# ngptv-lite-v11.net
KiCad netlist of a schematic drawn in EAGLE
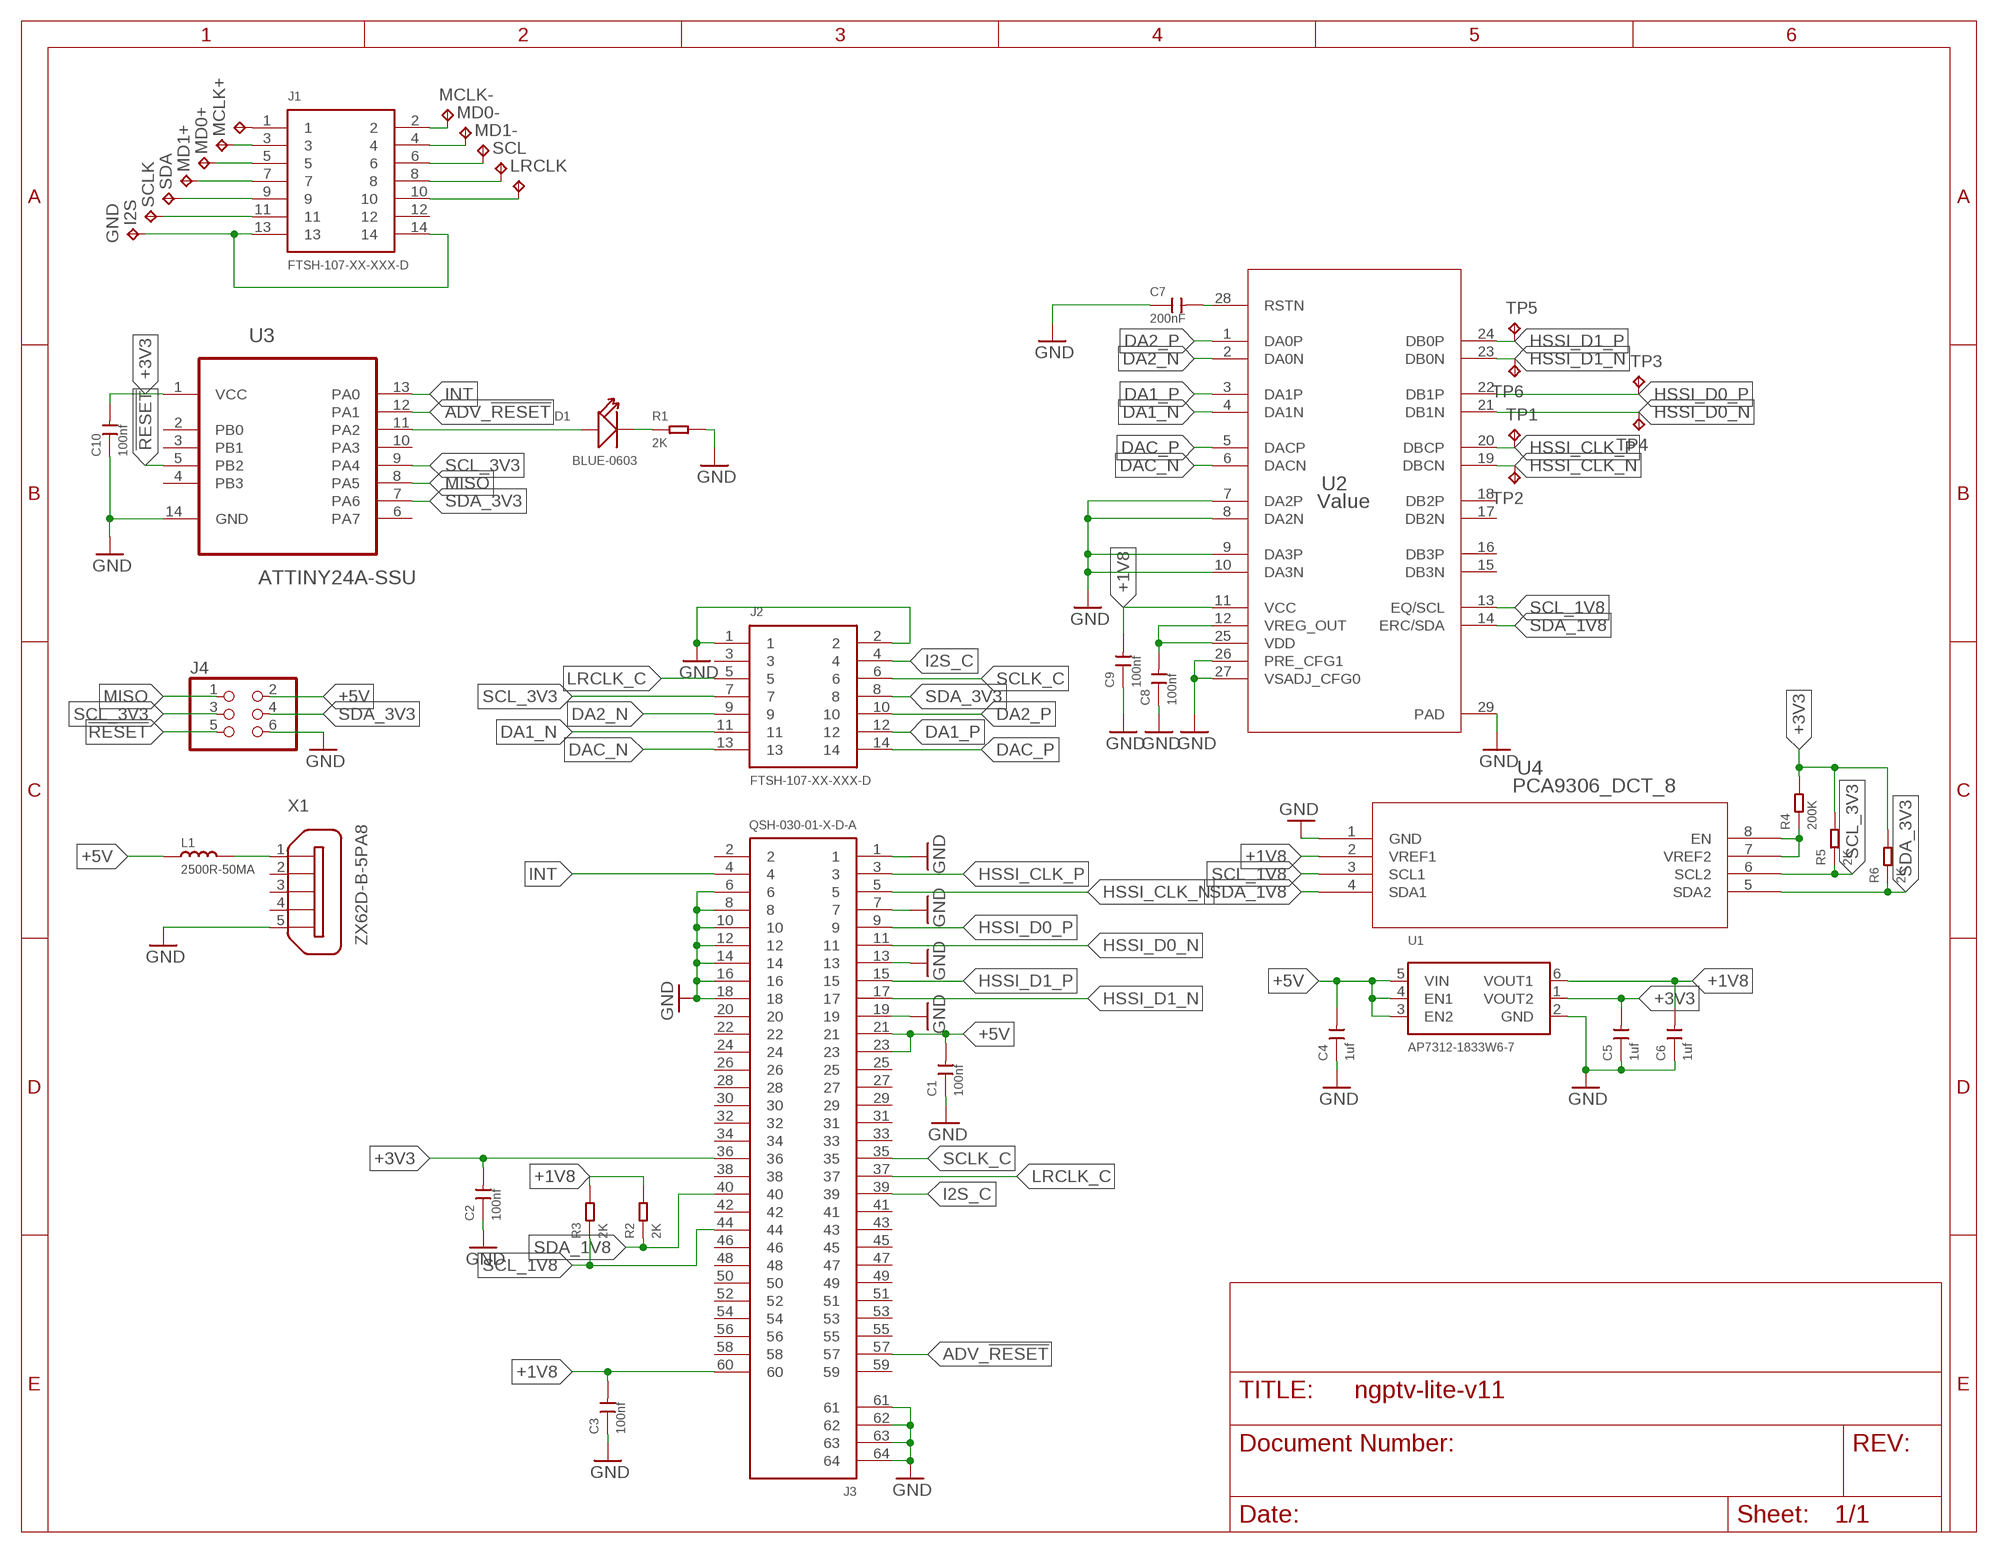
[diagram p0: schematic, sheet 1]

(export (version "E")
  (design (tool "Eeschema 10.0.6"))
  (components
    (comp (ref "C1")
      (value "100nf")
      (footprint "eagle-import:C0603")
      (fields (field (name "MPN") "CC0603KRX7R9BB104"))
      (libsource (lib "eagle-import") (part "CERAMIC-100NF-50V-10%-X7R(0603)"))
    )
    (comp (ref "C2")
      (value "100nf")
      (footprint "eagle-import:C0603")
      (fields (field (name "MPN") "CC0603KRX7R9BB104"))
      (libsource (lib "eagle-import") (part "CERAMIC-100NF-50V-10%-X7R(0603)"))
    )
    (comp (ref "C3")
      (value "100nf")
      (footprint "eagle-import:C0603")
      (fields (field (name "MPN") "CC0603KRX7R9BB104"))
      (libsource (lib "eagle-import") (part "CERAMIC-100NF-50V-10%-X7R(0603)"))
    )
    (comp (ref "C4")
      (value "1uf")
      (footprint "eagle-import:C0603")
      (fields (field (name "MPN") "CC0603KRX7R8BB105"))
      (libsource (lib "eagle-import") (part "CERAMIC-1UF-25V-10%-X7R(0603)"))
    )
    (comp (ref "C5")
      (value "1uf")
      (footprint "eagle-import:C0603")
      (fields (field (name "MPN") "CC0603KRX7R8BB105"))
      (libsource (lib "eagle-import") (part "CERAMIC-1UF-25V-10%-X7R(0603)"))
    )
    (comp (ref "C6")
      (value "1uf")
      (footprint "eagle-import:C0603")
      (fields (field (name "MPN") "CC0603KRX7R8BB105"))
      (libsource (lib "eagle-import") (part "CERAMIC-1UF-25V-10%-X7R(0603)"))
    )
    (comp (ref "C7")
      (value "200nF")
      (footprint "eagle-import:C0603")
      (fields (field (name "MPN") "CC0603KRX7R8BB224"))
      (libsource (lib "eagle-import") (part "CERAMIC-220NF-25V-10%-X7R(0603)"))
    )
    (comp (ref "C8")
      (value "100nf")
      (footprint "eagle-import:C0603")
      (fields (field (name "MPN") "CC0603KRX7R9BB104"))
      (libsource (lib "eagle-import") (part "CERAMIC-100NF-50V-10%-X7R(0603)"))
    )
    (comp (ref "C9")
      (value "100nf")
      (footprint "eagle-import:C0603")
      (fields (field (name "MPN") "CC0603KRX7R9BB104"))
      (libsource (lib "eagle-import") (part "CERAMIC-100NF-50V-10%-X7R(0603)"))
    )
    (comp (ref "C10")
      (value "100nf")
      (footprint "eagle-import:C0603")
      (fields (field (name "MPN") "CC0603KRX7R9BB104"))
      (libsource (lib "eagle-import") (part "CERAMIC-100NF-50V-10%-X7R(0603)"))
    )
    (comp (ref "D1")
      (value "BLUE-0603")
      (footprint "eagle-import:LED-0603")
      (fields (field (name "MPN") "19-217-BHC-ZL1M2RY-3T"))
      (libsource (lib "eagle-import") (part "SMD-LED-CLEAR-BLUE(0603)"))
    )
    (comp (ref "GND")
      (value "TPTP14R")
      (footprint "eagle-import:TP14R")
      (libsource (lib "eagle-import") (part "TPTP14R"))
    )
    (comp (ref "I2S")
      (value "TPTP12R")
      (footprint "eagle-import:TP12R")
      (libsource (lib "eagle-import") (part "TPTP12R"))
    )
    (comp (ref "J1")
      (value "FTSH-107-XX-XXX-D")
      (footprint "eagle-import:FTSH-107-XX-XXX-D")
      (libsource (lib "eagle-import") (part "FTSH-107-XX-XXX-D"))
    )
    (comp (ref "J2")
      (value "FTSH-107-XX-XXX-D")
      (footprint "eagle-import:FTSH-107-XX-XXX-D")
      (libsource (lib "eagle-import") (part "FTSH-107-XX-XXX-D"))
    )
    (comp (ref "J3")
      (value "QSH-030-01-X-D-A")
      (footprint "eagle-import:QSH-030-01-X-D-A")
      (libsource (lib "eagle-import") (part "QSH-030-01-X-D-A"))
    )
    (comp (ref "J4")
      (value "PINHD-2X3/90")
      (footprint "eagle-import:2X03_90")
      (libsource (lib "eagle-import") (part "PINHD-2X3/90"))
    )
    (comp (ref "L1")
      (value "2500R-50MA")
      (footprint "eagle-import:L0603")
      (libsource (lib "eagle-import") (part "SMD-FERRITE-BEAD-2500R-50MA(0603)"))
    )
    (comp (ref "LRCLK")
      (value "TPTP12R")
      (footprint "eagle-import:TP12R")
      (libsource (lib "eagle-import") (part "TPTP12R"))
    )
    (comp (ref "MCLK+")
      (value "TPTP12R")
      (footprint "eagle-import:TP12R")
      (libsource (lib "eagle-import") (part "TPTP12R"))
    )
    (comp (ref "MCLK-")
      (value "TPTP12R")
      (footprint "eagle-import:TP12R")
      (libsource (lib "eagle-import") (part "TPTP12R"))
    )
    (comp (ref "MD0+")
      (value "TPTP12R")
      (footprint "eagle-import:TP12R")
      (libsource (lib "eagle-import") (part "TPTP12R"))
    )
    (comp (ref "MD0-")
      (value "TPTP12R")
      (footprint "eagle-import:TP12R")
      (libsource (lib "eagle-import") (part "TPTP12R"))
    )
    (comp (ref "MD1+")
      (value "TPTP12R")
      (footprint "eagle-import:TP12R")
      (libsource (lib "eagle-import") (part "TPTP12R"))
    )
    (comp (ref "MD1-")
      (value "TPTP12R")
      (footprint "eagle-import:TP12R")
      (libsource (lib "eagle-import") (part "TPTP12R"))
    )
    (comp (ref "R1")
      (value "2K")
      (footprint "eagle-import:R0603")
      (fields (field (name "MPN") "RC0603FR-071KL"))
      (libsource (lib "eagle-import") (part "SMD-RES-1K-1%-1/10W(0603)"))
    )
    (comp (ref "R2")
      (value "2K")
      (footprint "eagle-import:R0603")
      (fields (field (name "MPN") "RC0603JR-072KL"))
      (libsource (lib "eagle-import") (part "SMD-RES-2K-5%-1/10W(0603)"))
    )
    (comp (ref "R3")
      (value "2K")
      (footprint "eagle-import:R0603")
      (fields (field (name "MPN") "RC0603JR-072KL"))
      (libsource (lib "eagle-import") (part "SMD-RES-2K-5%-1/10W(0603)"))
    )
    (comp (ref "R4")
      (value "200K")
      (footprint "eagle-import:R0603")
      (fields (field (name "MPN") "RC0603JR-07200KL"))
      (libsource (lib "eagle-import") (part "SMD-RES-200K-5%-1/10W(0603)"))
    )
    (comp (ref "R5")
      (value "2K")
      (footprint "eagle-import:R0603")
      (fields (field (name "MPN") "RC0603JR-072KL"))
      (libsource (lib "eagle-import") (part "SMD-RES-2K-5%-1/10W(0603)"))
    )
    (comp (ref "R6")
      (value "2K")
      (footprint "eagle-import:R0603")
      (fields (field (name "MPN") "RC0603JR-072KL"))
      (libsource (lib "eagle-import") (part "SMD-RES-2K-5%-1/10W(0603)"))
    )
    (comp (ref "SCL")
      (value "TPTP12R")
      (footprint "eagle-import:TP12R")
      (libsource (lib "eagle-import") (part "TPTP12R"))
    )
    (comp (ref "SCLK")
      (value "TPTP12R")
      (footprint "eagle-import:TP12R")
      (libsource (lib "eagle-import") (part "TPTP12R"))
    )
    (comp (ref "SDA")
      (value "TPTP12R")
      (footprint "eagle-import:TP12R")
      (libsource (lib "eagle-import") (part "TPTP12R"))
    )
    (comp (ref "TP1")
      (value "TPTP06SQ")
      (footprint "eagle-import:TP06SQ")
      (libsource (lib "eagle-import") (part "TPTP06SQ"))
    )
    (comp (ref "TP2")
      (value "TPTP06SQ")
      (footprint "eagle-import:TP06SQ")
      (libsource (lib "eagle-import") (part "TPTP06SQ"))
    )
    (comp (ref "TP3")
      (value "TPTP06SQ")
      (footprint "eagle-import:TP06SQ")
      (libsource (lib "eagle-import") (part "TPTP06SQ"))
    )
    (comp (ref "TP4")
      (value "TPTP06SQ")
      (footprint "eagle-import:TP06SQ")
      (libsource (lib "eagle-import") (part "TPTP06SQ"))
    )
    (comp (ref "TP5")
      (value "TPTP06SQ")
      (footprint "eagle-import:TP06SQ")
      (libsource (lib "eagle-import") (part "TPTP06SQ"))
    )
    (comp (ref "TP6")
      (value "TPTP06SQ")
      (footprint "eagle-import:TP06SQ")
      (libsource (lib "eagle-import") (part "TPTP06SQ"))
    )
    (comp (ref "U1")
      (value "AP7312-1833W6-7")
      (footprint "eagle-import:SOT95P280X145-6N")
      (libsource (lib "eagle-import") (part "AP7312"))
    )
    (comp (ref "U2")
      (value "Value")
      (footprint "eagle-import:RHR0028A_NV")
      (fields
        (field (name "ALTERNATEPARTNUMBER") "SN65DPHY440SS")
        (field (name "MANUFACTURER") "Texas Instruments")
        (field (name "PARTNUMBER") "SN75DPHY440SS")
      )
      (libsource (lib "eagle-import") (part "SN75DPHY440SS"))
    )
    (comp (ref "U3")
      (value "ATTINY24A-SSU")
      (footprint "eagle-import:SOIC127P600X175-14N")
      (libsource (lib "eagle-import") (part "ATTINY24A-SSU"))
    )
    (comp (ref "U4")
      (value "PCA9306_DCT_8")
      (footprint "eagle-import:DCT8")
      (fields
        (field (name "GENERIC_PART_NUMBER") "PCA9306")
        (field (name "MANUFACTURER") "Texas Instruments")
        (field (name "MANUFACTURER_PART_NUMBER") "pca9306_dct_8")
      )
      (libsource (lib "eagle-import") (part "PCA9306_DCT_8"))
    )
    (comp (ref "X1")
      (value "ZX62D-B-5PA8")
      (footprint "eagle-import:ZX62D-B-5PA8")
      (fields (field (name "MF") "Hirose"))
      (libsource (lib "eagle-import") (part "ZX62D-B-5PA8"))
    )
  )
  (nets
    (net (code "1") (name "+1V8") (class "Default")
      (node (ref "C3") (pin "2") (pinfunction "2_2") (pintype "passive"))
      (node (ref "C6") (pin "2") (pinfunction "2_2") (pintype "passive"))
      (node (ref "C9") (pin "2") (pinfunction "2_2") (pintype "passive"))
      (node (ref "J3") (pin "60") (pinfunction "60_60") (pintype "bidirectional"))
      (node (ref "R2") (pin "2") (pinfunction "2_2") (pintype "passive"))
      (node (ref "R3") (pin "2") (pinfunction "2_2") (pintype "passive"))
      (node (ref "U1") (pin "6") (pinfunction "VOUT1_6") (pintype "power_in"))
      (node (ref "U2") (pin "11") (pinfunction "VCC_11") (pintype "power_in"))
      (node (ref "U4") (pin "2") (pinfunction "VREF1_2") (pintype "power_in"))
    )
    (net (code "2") (name "+3V3") (class "Default")
      (node (ref "C10") (pin "2") (pinfunction "2_2") (pintype "passive"))
      (node (ref "C2") (pin "2") (pinfunction "2_2") (pintype "passive"))
      (node (ref "C5") (pin "2") (pinfunction "2_2") (pintype "passive"))
      (node (ref "J3") (pin "36") (pinfunction "36_36") (pintype "bidirectional"))
      (node (ref "R4") (pin "2") (pinfunction "2_2") (pintype "passive"))
      (node (ref "R5") (pin "2") (pinfunction "2_2") (pintype "passive"))
      (node (ref "R6") (pin "2") (pinfunction "2_2") (pintype "passive"))
      (node (ref "U1") (pin "1") (pinfunction "VOUT2_1") (pintype "power_in"))
      (node (ref "U3") (pin "1") (pinfunction "VCC_1") (pintype "power_in"))
    )
    (net (code "3") (name "+5V") (class "Default")
      (node (ref "C1") (pin "2") (pinfunction "2_2") (pintype "passive"))
      (node (ref "C4") (pin "2") (pinfunction "2_2") (pintype "passive"))
      (node (ref "J3") (pin "21") (pinfunction "21_21") (pintype "bidirectional"))
      (node (ref "J3") (pin "23") (pinfunction "23_23") (pintype "bidirectional"))
      (node (ref "J4") (pin "2") (pinfunction "2_2") (pintype "passive"))
      (node (ref "L1") (pin "1") (pinfunction "1_1") (pintype "passive"))
      (node (ref "U1") (pin "3") (pinfunction "EN2_3") (pintype "bidirectional"))
      (node (ref "U1") (pin "4") (pinfunction "EN1_4") (pintype "bidirectional"))
      (node (ref "U1") (pin "5") (pinfunction "VIN_5") (pintype "power_in"))
    )
    (net (code "4") (name "/ADV_~{RESET}") (class "Default")
      (node (ref "J3") (pin "57") (pinfunction "57_57") (pintype "bidirectional"))
      (node (ref "U3") (pin "12") (pinfunction "PA1_12") (pintype "bidirectional"))
    )
    (net (code "5") (name "/~{RESET}") (class "Default")
      (node (ref "J4") (pin "5") (pinfunction "5_5") (pintype "passive"))
      (node (ref "U3") (pin "5") (pinfunction "PB2_5") (pintype "bidirectional"))
    )
    (net (code "6") (name "DA1_N") (class "Default")
      (node (ref "J2") (pin "11") (pinfunction "11_11") (pintype "bidirectional"))
      (node (ref "U2") (pin "4") (pinfunction "DA1N_4") (pintype "bidirectional"))
    )
    (net (code "7") (name "DA1_P") (class "Default")
      (node (ref "J2") (pin "12") (pinfunction "12_12") (pintype "bidirectional"))
      (node (ref "U2") (pin "3") (pinfunction "DA1P_3") (pintype "bidirectional"))
    )
    (net (code "8") (name "DA2_N") (class "Default")
      (node (ref "J2") (pin "9") (pinfunction "9_9") (pintype "bidirectional"))
      (node (ref "U2") (pin "2") (pinfunction "DA0N_2") (pintype "bidirectional"))
    )
    (net (code "9") (name "DA2_P") (class "Default")
      (node (ref "J2") (pin "10") (pinfunction "10_10") (pintype "bidirectional"))
      (node (ref "U2") (pin "1") (pinfunction "DA0P_1") (pintype "bidirectional"))
    )
    (net (code "10") (name "DAC_N") (class "Default")
      (node (ref "J2") (pin "13") (pinfunction "13_13") (pintype "bidirectional"))
      (node (ref "U2") (pin "6") (pinfunction "DACN_6") (pintype "bidirectional"))
    )
    (net (code "11") (name "DAC_P") (class "Default")
      (node (ref "J2") (pin "14") (pinfunction "14_14") (pintype "bidirectional"))
      (node (ref "U2") (pin "5") (pinfunction "DACP_5") (pintype "bidirectional"))
    )
    (net (code "12") (name "GND") (class "Default")
      (node (ref "C1") (pin "1") (pinfunction "1_1") (pintype "passive"))
      (node (ref "C10") (pin "1") (pinfunction "1_1") (pintype "passive"))
      (node (ref "C2") (pin "1") (pinfunction "1_1") (pintype "passive"))
      (node (ref "C3") (pin "1") (pinfunction "1_1") (pintype "passive"))
      (node (ref "C4") (pin "1") (pinfunction "1_1") (pintype "passive"))
      (node (ref "C5") (pin "1") (pinfunction "1_1") (pintype "passive"))
      (node (ref "C6") (pin "1") (pinfunction "1_1") (pintype "passive"))
      (node (ref "C7") (pin "1") (pinfunction "1_1") (pintype "passive"))
      (node (ref "C8") (pin "1") (pinfunction "1_1") (pintype "passive"))
      (node (ref "C9") (pin "1") (pinfunction "1_1") (pintype "passive"))
      (node (ref "J2") (pin "1") (pinfunction "1_1") (pintype "bidirectional"))
      (node (ref "J2") (pin "2") (pinfunction "2_2") (pintype "bidirectional"))
      (node (ref "J3") (pin "1") (pinfunction "1_1") (pintype "bidirectional"))
      (node (ref "J3") (pin "10") (pinfunction "10_10") (pintype "bidirectional"))
      (node (ref "J3") (pin "12") (pinfunction "12_12") (pintype "bidirectional"))
      (node (ref "J3") (pin "13") (pinfunction "13_13") (pintype "bidirectional"))
      (node (ref "J3") (pin "14") (pinfunction "14_14") (pintype "bidirectional"))
      (node (ref "J3") (pin "16") (pinfunction "16_16") (pintype "bidirectional"))
      (node (ref "J3") (pin "18") (pinfunction "18_18") (pintype "bidirectional"))
      (node (ref "J3") (pin "19") (pinfunction "19_19") (pintype "bidirectional"))
      (node (ref "J3") (pin "6") (pinfunction "6_6") (pintype "bidirectional"))
      (node (ref "J3") (pin "61") (pinfunction "61_61") (pintype "power_in"))
      (node (ref "J3") (pin "62") (pinfunction "62_62") (pintype "power_in"))
      (node (ref "J3") (pin "63") (pinfunction "63_63") (pintype "power_in"))
      (node (ref "J3") (pin "64") (pinfunction "64_64") (pintype "power_in"))
      (node (ref "J3") (pin "7") (pinfunction "7_7") (pintype "bidirectional"))
      (node (ref "J3") (pin "8") (pinfunction "8_8") (pintype "bidirectional"))
      (node (ref "J4") (pin "6") (pinfunction "6_6") (pintype "passive"))
      (node (ref "R1") (pin "2") (pinfunction "2_2") (pintype "passive"))
      (node (ref "U1") (pin "2") (pinfunction "GND_2") (pintype "bidirectional"))
      (node (ref "U2") (pin "10") (pinfunction "DA3N_10") (pintype "bidirectional"))
      (node (ref "U2") (pin "26") (pinfunction "PRE_CFG1_26") (pintype "bidirectional"))
      (node (ref "U2") (pin "27") (pinfunction "VSADJ_CFG0_27") (pintype "bidirectional"))
      (node (ref "U2") (pin "29") (pinfunction "PAD_29") (pintype "power_in"))
      (node (ref "U2") (pin "7") (pinfunction "DA2P_7") (pintype "bidirectional"))
      (node (ref "U2") (pin "8") (pinfunction "DA2N_8") (pintype "bidirectional"))
      (node (ref "U2") (pin "9") (pinfunction "DA3P_9") (pintype "bidirectional"))
      (node (ref "U3") (pin "14") (pinfunction "GND_14") (pintype "power_in"))
      (node (ref "U4") (pin "1") (pinfunction "GND_1") (pintype "power_in"))
      (node (ref "X1") (pin "5") (pinfunction "5_5") (pintype "passive"))
    )
    (net (code "13") (name "HSSI_CLK_N") (class "Default")
      (node (ref "J3") (pin "5") (pinfunction "5_5") (pintype "bidirectional"))
      (node (ref "TP2") (pin "TP") (pinfunction "TP_TP") (pintype "input"))
      (node (ref "U2") (pin "19") (pinfunction "DBCN_19") (pintype "bidirectional"))
    )
    (net (code "14") (name "HSSI_CLK_P") (class "Default")
      (node (ref "J3") (pin "3") (pinfunction "3_3") (pintype "bidirectional"))
      (node (ref "TP1") (pin "TP") (pinfunction "TP_TP") (pintype "input"))
      (node (ref "U2") (pin "20") (pinfunction "DBCP_20") (pintype "bidirectional"))
    )
    (net (code "15") (name "HSSI_D0_N") (class "Default")
      (node (ref "J3") (pin "11") (pinfunction "11_11") (pintype "bidirectional"))
      (node (ref "TP4") (pin "TP") (pinfunction "TP_TP") (pintype "input"))
      (node (ref "U2") (pin "21") (pinfunction "DB1N_21") (pintype "bidirectional"))
    )
    (net (code "16") (name "HSSI_D0_P") (class "Default")
      (node (ref "J3") (pin "9") (pinfunction "9_9") (pintype "bidirectional"))
      (node (ref "TP3") (pin "TP") (pinfunction "TP_TP") (pintype "input"))
      (node (ref "U2") (pin "22") (pinfunction "DB1P_22") (pintype "bidirectional"))
    )
    (net (code "17") (name "HSSI_D1_N") (class "Default")
      (node (ref "J3") (pin "17") (pinfunction "17_17") (pintype "bidirectional"))
      (node (ref "TP6") (pin "TP") (pinfunction "TP_TP") (pintype "input"))
      (node (ref "U2") (pin "23") (pinfunction "DB0N_23") (pintype "bidirectional"))
    )
    (net (code "18") (name "HSSI_D1_P") (class "Default")
      (node (ref "J3") (pin "15") (pinfunction "15_15") (pintype "bidirectional"))
      (node (ref "TP5") (pin "TP") (pinfunction "TP_TP") (pintype "input"))
      (node (ref "U2") (pin "24") (pinfunction "DB0P_24") (pintype "bidirectional"))
    )
    (net (code "19") (name "I2S_C") (class "Default")
      (node (ref "J2") (pin "4") (pinfunction "4_4") (pintype "bidirectional"))
      (node (ref "J3") (pin "39") (pinfunction "39_39") (pintype "bidirectional"))
    )
    (net (code "20") (name "INT") (class "Default")
      (node (ref "J3") (pin "4") (pinfunction "4_4") (pintype "bidirectional"))
      (node (ref "U3") (pin "13") (pinfunction "PA0_13") (pintype "bidirectional"))
    )
    (net (code "21") (name "LRCLK_C") (class "Default")
      (node (ref "J2") (pin "5") (pinfunction "5_5") (pintype "bidirectional"))
      (node (ref "J3") (pin "37") (pinfunction "37_37") (pintype "bidirectional"))
    )
    (net (code "22") (name "MISO") (class "Default")
      (node (ref "J4") (pin "1") (pinfunction "1_1") (pintype "passive"))
      (node (ref "U3") (pin "8") (pinfunction "PA5_8") (pintype "bidirectional"))
    )
    (net (code "23") (name "Net-(D1-Pad-)") (class "Default")
      (node (ref "D1") (pin "-") (pinfunction "-_-") (pintype "passive"))
      (node (ref "R1") (pin "1") (pinfunction "1_1") (pintype "passive"))
    )
    (net (code "24") (name "Net-(GND-PadTP)") (class "Default")
      (node (ref "GND") (pin "TP") (pinfunction "TP_TP") (pintype "input"))
      (node (ref "J1") (pin "13") (pinfunction "13_13") (pintype "bidirectional"))
      (node (ref "J1") (pin "14") (pinfunction "14_14") (pintype "bidirectional"))
    )
    (net (code "25") (name "Net-(I2S-PadTP)") (class "Default")
      (node (ref "I2S") (pin "TP") (pinfunction "TP_TP") (pintype "input"))
      (node (ref "J1") (pin "11") (pinfunction "11_11") (pintype "bidirectional"))
    )
    (net (code "26") (name "Net-(J1-Pad1)") (class "Default")
      (node (ref "J1") (pin "1") (pinfunction "1_1") (pintype "bidirectional"))
      (node (ref "MCLK+") (pin "TP") (pinfunction "TP_TP") (pintype "input"))
    )
    (net (code "27") (name "Net-(J1-Pad2)") (class "Default")
      (node (ref "J1") (pin "2") (pinfunction "2_2") (pintype "bidirectional"))
      (node (ref "MCLK-") (pin "TP") (pinfunction "TP_TP") (pintype "input"))
    )
    (net (code "28") (name "Net-(J1-Pad3)") (class "Default")
      (node (ref "J1") (pin "3") (pinfunction "3_3") (pintype "bidirectional"))
      (node (ref "MD0+") (pin "TP") (pinfunction "TP_TP") (pintype "input"))
    )
    (net (code "29") (name "Net-(J1-Pad4)") (class "Default")
      (node (ref "J1") (pin "4") (pinfunction "4_4") (pintype "bidirectional"))
      (node (ref "MD0-") (pin "TP") (pinfunction "TP_TP") (pintype "input"))
    )
    (net (code "30") (name "Net-(J1-Pad5)") (class "Default")
      (node (ref "J1") (pin "5") (pinfunction "5_5") (pintype "bidirectional"))
      (node (ref "MD1+") (pin "TP") (pinfunction "TP_TP") (pintype "input"))
    )
    (net (code "31") (name "Net-(J1-Pad6)") (class "Default")
      (node (ref "J1") (pin "6") (pinfunction "6_6") (pintype "bidirectional"))
      (node (ref "MD1-") (pin "TP") (pinfunction "TP_TP") (pintype "input"))
    )
    (net (code "32") (name "Net-(J1-Pad7)") (class "Default")
      (node (ref "J1") (pin "7") (pinfunction "7_7") (pintype "bidirectional"))
      (node (ref "SDA") (pin "TP") (pinfunction "TP_TP") (pintype "input"))
    )
    (net (code "33") (name "Net-(J1-Pad8)") (class "Default")
      (node (ref "J1") (pin "8") (pinfunction "8_8") (pintype "bidirectional"))
      (node (ref "SCL") (pin "TP") (pinfunction "TP_TP") (pintype "input"))
    )
    (net (code "34") (name "Net-(J1-Pad9)") (class "Default")
      (node (ref "J1") (pin "9") (pinfunction "9_9") (pintype "bidirectional"))
      (node (ref "SCLK") (pin "TP") (pinfunction "TP_TP") (pintype "input"))
    )
    (net (code "35") (name "Net-(J1-Pad10)") (class "Default")
      (node (ref "J1") (pin "10") (pinfunction "10_10") (pintype "bidirectional"))
      (node (ref "LRCLK") (pin "TP") (pinfunction "TP_TP") (pintype "input"))
    )
    (net (code "36") (name "Net-(L1-Pad2)") (class "Default")
      (node (ref "L1") (pin "2") (pinfunction "2_2") (pintype "passive"))
      (node (ref "X1") (pin "1") (pinfunction "1_1") (pintype "passive"))
    )
    (net (code "37") (name "Net-(U2-RSTN)") (class "Default")
      (node (ref "C7") (pin "2") (pinfunction "2_2") (pintype "passive"))
      (node (ref "U2") (pin "28") (pinfunction "RSTN_28") (pintype "bidirectional"))
    )
    (net (code "38") (name "Net-(U2-VDD)") (class "Default")
      (node (ref "C8") (pin "2") (pinfunction "2_2") (pintype "passive"))
      (node (ref "U2") (pin "12") (pinfunction "VREG_OUT_12") (pintype "power_in"))
      (node (ref "U2") (pin "25") (pinfunction "VDD_25") (pintype "power_in"))
    )
    (net (code "39") (name "Net-(U3-PA2)") (class "Default")
      (node (ref "D1") (pin "+") (pinfunction "+_+") (pintype "passive"))
      (node (ref "U3") (pin "11") (pinfunction "PA2_11") (pintype "bidirectional"))
    )
    (net (code "40") (name "Net-(U4-EN)") (class "Default")
      (node (ref "R4") (pin "1") (pinfunction "1_1") (pintype "passive"))
      (node (ref "U4") (pin "7") (pinfunction "VREF2_7") (pintype "power_in"))
      (node (ref "U4") (pin "8") (pinfunction "EN_8") (pintype "passive"))
    )
    (net (code "41") (name "SCLK_C") (class "Default")
      (node (ref "J2") (pin "6") (pinfunction "6_6") (pintype "bidirectional"))
      (node (ref "J3") (pin "35") (pinfunction "35_35") (pintype "bidirectional"))
    )
    (net (code "42") (name "SCL_1V8") (class "Default")
      (node (ref "J3") (pin "44") (pinfunction "44_44") (pintype "bidirectional"))
      (node (ref "R3") (pin "1") (pinfunction "1_1") (pintype "passive"))
      (node (ref "U2") (pin "13") (pinfunction "EQ/SCL_13") (pintype "bidirectional"))
      (node (ref "U4") (pin "3") (pinfunction "SCL1_3") (pintype "passive"))
    )
    (net (code "43") (name "SCL_3V3") (class "Default")
      (node (ref "J2") (pin "7") (pinfunction "7_7") (pintype "bidirectional"))
      (node (ref "J4") (pin "3") (pinfunction "3_3") (pintype "passive"))
      (node (ref "R5") (pin "1") (pinfunction "1_1") (pintype "passive"))
      (node (ref "U3") (pin "9") (pinfunction "PA4_9") (pintype "bidirectional"))
      (node (ref "U4") (pin "6") (pinfunction "SCL2_6") (pintype "passive"))
    )
    (net (code "44") (name "SDA_1V8") (class "Default")
      (node (ref "J3") (pin "40") (pinfunction "40_40") (pintype "bidirectional"))
      (node (ref "R2") (pin "1") (pinfunction "1_1") (pintype "passive"))
      (node (ref "U2") (pin "14") (pinfunction "ERC/SDA_14") (pintype "bidirectional"))
      (node (ref "U4") (pin "4") (pinfunction "SDA1_4") (pintype "passive"))
    )
    (net (code "45") (name "SDA_3V3") (class "Default")
      (node (ref "J2") (pin "8") (pinfunction "8_8") (pintype "bidirectional"))
      (node (ref "J4") (pin "4") (pinfunction "4_4") (pintype "passive"))
      (node (ref "R6") (pin "1") (pinfunction "1_1") (pintype "passive"))
      (node (ref "U3") (pin "7") (pinfunction "PA6_7") (pintype "bidirectional"))
      (node (ref "U4") (pin "5") (pinfunction "SDA2_5") (pintype "passive"))
    )
    (net (code "46") (name "unconnected-(J1-Pad12)") (class "Default")
      (node (ref "J1") (pin "12") (pinfunction "12_12") (pintype "bidirectional"))
    )
    (net (code "47") (name "unconnected-(J2-Pad3)") (class "Default")
      (node (ref "J2") (pin "3") (pinfunction "3_3") (pintype "bidirectional"))
    )
    (net (code "48") (name "unconnected-(J3-Pad2)") (class "Default")
      (node (ref "J3") (pin "2") (pinfunction "2_2") (pintype "bidirectional"))
    )
    (net (code "49") (name "unconnected-(J3-Pad20)") (class "Default")
      (node (ref "J3") (pin "20") (pinfunction "20_20") (pintype "bidirectional"))
    )
    (net (code "50") (name "unconnected-(J3-Pad22)") (class "Default")
      (node (ref "J3") (pin "22") (pinfunction "22_22") (pintype "bidirectional"))
    )
    (net (code "51") (name "unconnected-(J3-Pad24)") (class "Default")
      (node (ref "J3") (pin "24") (pinfunction "24_24") (pintype "bidirectional"))
    )
    (net (code "52") (name "unconnected-(J3-Pad25)") (class "Default")
      (node (ref "J3") (pin "25") (pinfunction "25_25") (pintype "bidirectional"))
    )
    (net (code "53") (name "unconnected-(J3-Pad26)") (class "Default")
      (node (ref "J3") (pin "26") (pinfunction "26_26") (pintype "bidirectional"))
    )
    (net (code "54") (name "unconnected-(J3-Pad27)") (class "Default")
      (node (ref "J3") (pin "27") (pinfunction "27_27") (pintype "bidirectional"))
    )
    (net (code "55") (name "unconnected-(J3-Pad28)") (class "Default")
      (node (ref "J3") (pin "28") (pinfunction "28_28") (pintype "bidirectional"))
    )
    (net (code "56") (name "unconnected-(J3-Pad29)") (class "Default")
      (node (ref "J3") (pin "29") (pinfunction "29_29") (pintype "bidirectional"))
    )
    (net (code "57") (name "unconnected-(J3-Pad30)") (class "Default")
      (node (ref "J3") (pin "30") (pinfunction "30_30") (pintype "bidirectional"))
    )
    (net (code "58") (name "unconnected-(J3-Pad31)") (class "Default")
      (node (ref "J3") (pin "31") (pinfunction "31_31") (pintype "bidirectional"))
    )
    (net (code "59") (name "unconnected-(J3-Pad32)") (class "Default")
      (node (ref "J3") (pin "32") (pinfunction "32_32") (pintype "bidirectional"))
    )
    (net (code "60") (name "unconnected-(J3-Pad33)") (class "Default")
      (node (ref "J3") (pin "33") (pinfunction "33_33") (pintype "bidirectional"))
    )
    (net (code "61") (name "unconnected-(J3-Pad34)") (class "Default")
      (node (ref "J3") (pin "34") (pinfunction "34_34") (pintype "bidirectional"))
    )
    (net (code "62") (name "unconnected-(J3-Pad38)") (class "Default")
      (node (ref "J3") (pin "38") (pinfunction "38_38") (pintype "bidirectional"))
    )
    (net (code "63") (name "unconnected-(J3-Pad41)") (class "Default")
      (node (ref "J3") (pin "41") (pinfunction "41_41") (pintype "bidirectional"))
    )
    (net (code "64") (name "unconnected-(J3-Pad42)") (class "Default")
      (node (ref "J3") (pin "42") (pinfunction "42_42") (pintype "bidirectional"))
    )
    (net (code "65") (name "unconnected-(J3-Pad43)") (class "Default")
      (node (ref "J3") (pin "43") (pinfunction "43_43") (pintype "bidirectional"))
    )
    (net (code "66") (name "unconnected-(J3-Pad45)") (class "Default")
      (node (ref "J3") (pin "45") (pinfunction "45_45") (pintype "bidirectional"))
    )
    (net (code "67") (name "unconnected-(J3-Pad46)") (class "Default")
      (node (ref "J3") (pin "46") (pinfunction "46_46") (pintype "bidirectional"))
    )
    (net (code "68") (name "unconnected-(J3-Pad47)") (class "Default")
      (node (ref "J3") (pin "47") (pinfunction "47_47") (pintype "bidirectional"))
    )
    (net (code "69") (name "unconnected-(J3-Pad48)") (class "Default")
      (node (ref "J3") (pin "48") (pinfunction "48_48") (pintype "bidirectional"))
    )
    (net (code "70") (name "unconnected-(J3-Pad49)") (class "Default")
      (node (ref "J3") (pin "49") (pinfunction "49_49") (pintype "bidirectional"))
    )
    (net (code "71") (name "unconnected-(J3-Pad50)") (class "Default")
      (node (ref "J3") (pin "50") (pinfunction "50_50") (pintype "bidirectional"))
    )
    (net (code "72") (name "unconnected-(J3-Pad51)") (class "Default")
      (node (ref "J3") (pin "51") (pinfunction "51_51") (pintype "bidirectional"))
    )
    (net (code "73") (name "unconnected-(J3-Pad52)") (class "Default")
      (node (ref "J3") (pin "52") (pinfunction "52_52") (pintype "bidirectional"))
    )
    (net (code "74") (name "unconnected-(J3-Pad53)") (class "Default")
      (node (ref "J3") (pin "53") (pinfunction "53_53") (pintype "bidirectional"))
    )
    (net (code "75") (name "unconnected-(J3-Pad54)") (class "Default")
      (node (ref "J3") (pin "54") (pinfunction "54_54") (pintype "bidirectional"))
    )
    (net (code "76") (name "unconnected-(J3-Pad55)") (class "Default")
      (node (ref "J3") (pin "55") (pinfunction "55_55") (pintype "bidirectional"))
    )
    (net (code "77") (name "unconnected-(J3-Pad56)") (class "Default")
      (node (ref "J3") (pin "56") (pinfunction "56_56") (pintype "bidirectional"))
    )
    (net (code "78") (name "unconnected-(J3-Pad58)") (class "Default")
      (node (ref "J3") (pin "58") (pinfunction "58_58") (pintype "bidirectional"))
    )
    (net (code "79") (name "unconnected-(J3-Pad59)") (class "Default")
      (node (ref "J3") (pin "59") (pinfunction "59_59") (pintype "bidirectional"))
    )
    (net (code "80") (name "unconnected-(U2-DB2N-Pad17)") (class "Default")
      (node (ref "U2") (pin "17") (pinfunction "DB2N_17") (pintype "bidirectional"))
    )
    (net (code "81") (name "unconnected-(U2-DB2P-Pad18)") (class "Default")
      (node (ref "U2") (pin "18") (pinfunction "DB2P_18") (pintype "bidirectional"))
    )
    (net (code "82") (name "unconnected-(U2-DB3N-Pad15)") (class "Default")
      (node (ref "U2") (pin "15") (pinfunction "DB3N_15") (pintype "bidirectional"))
    )
    (net (code "83") (name "unconnected-(U2-DB3P-Pad16)") (class "Default")
      (node (ref "U2") (pin "16") (pinfunction "DB3P_16") (pintype "bidirectional"))
    )
    (net (code "84") (name "unconnected-(U3-PA3-Pad10)") (class "Default")
      (node (ref "U3") (pin "10") (pinfunction "PA3_10") (pintype "bidirectional"))
    )
    (net (code "85") (name "unconnected-(U3-PA7-Pad6)") (class "Default")
      (node (ref "U3") (pin "6") (pinfunction "PA7_6") (pintype "bidirectional"))
    )
    (net (code "86") (name "unconnected-(U3-PB0-Pad2)") (class "Default")
      (node (ref "U3") (pin "2") (pinfunction "PB0_2") (pintype "bidirectional"))
    )
    (net (code "87") (name "unconnected-(U3-PB1-Pad3)") (class "Default")
      (node (ref "U3") (pin "3") (pinfunction "PB1_3") (pintype "bidirectional"))
    )
    (net (code "88") (name "unconnected-(U3-PB3-Pad4)") (class "Default")
      (node (ref "U3") (pin "4") (pinfunction "PB3_4") (pintype "bidirectional"))
    )
    (net (code "89") (name "unconnected-(X1-Pad2)") (class "Default")
      (node (ref "X1") (pin "2") (pinfunction "2_2") (pintype "passive"))
    )
    (net (code "90") (name "unconnected-(X1-Pad3)") (class "Default")
      (node (ref "X1") (pin "3") (pinfunction "3_3") (pintype "passive"))
    )
    (net (code "91") (name "unconnected-(X1-Pad4)") (class "Default")
      (node (ref "X1") (pin "4") (pinfunction "4_4") (pintype "passive"))
    )
  )
)
